# componentes1.net
KiCad netlist of a schematic drawn in EAGLE
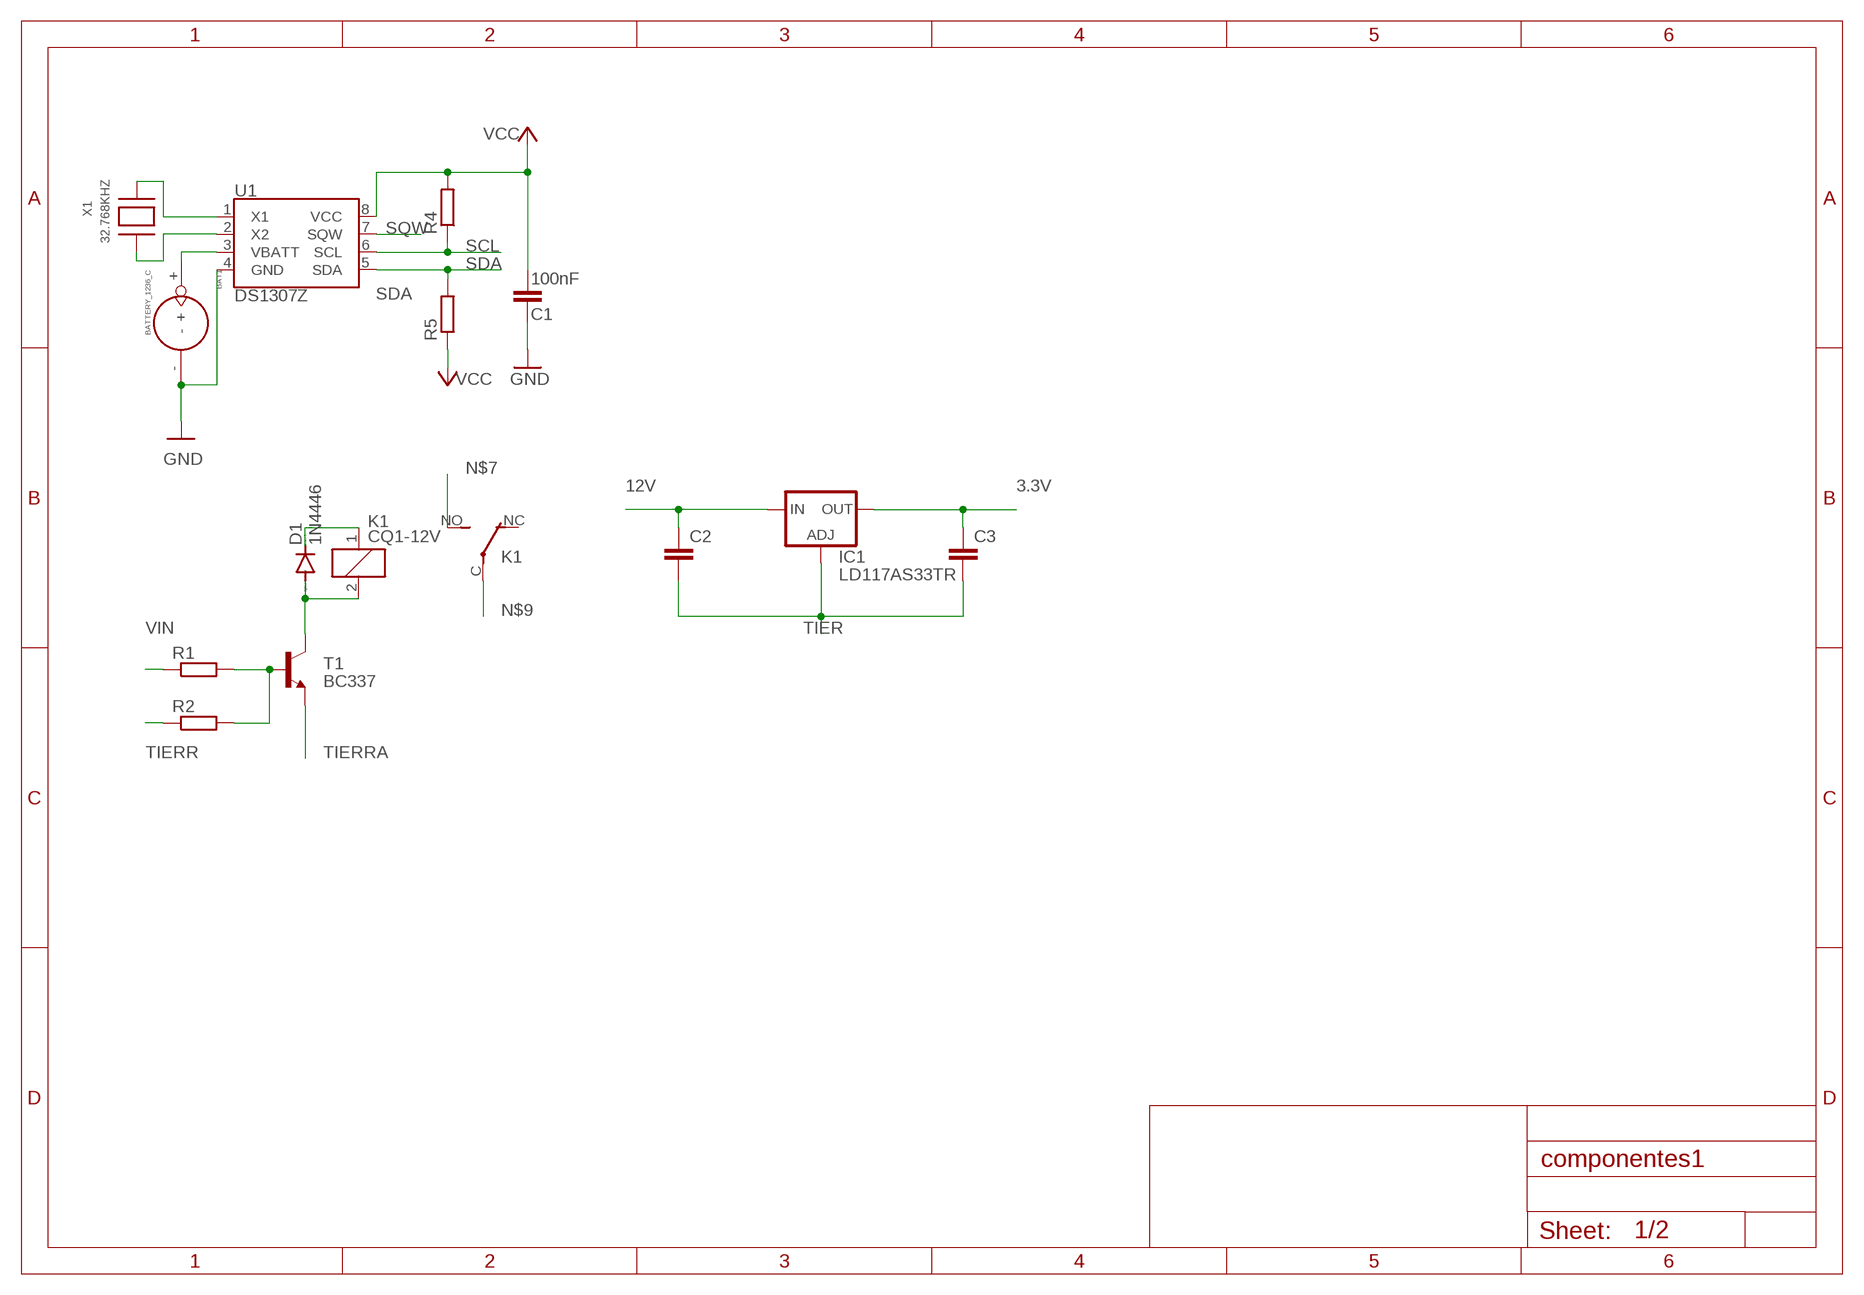
[diagram p0: schematic, sheet 1]
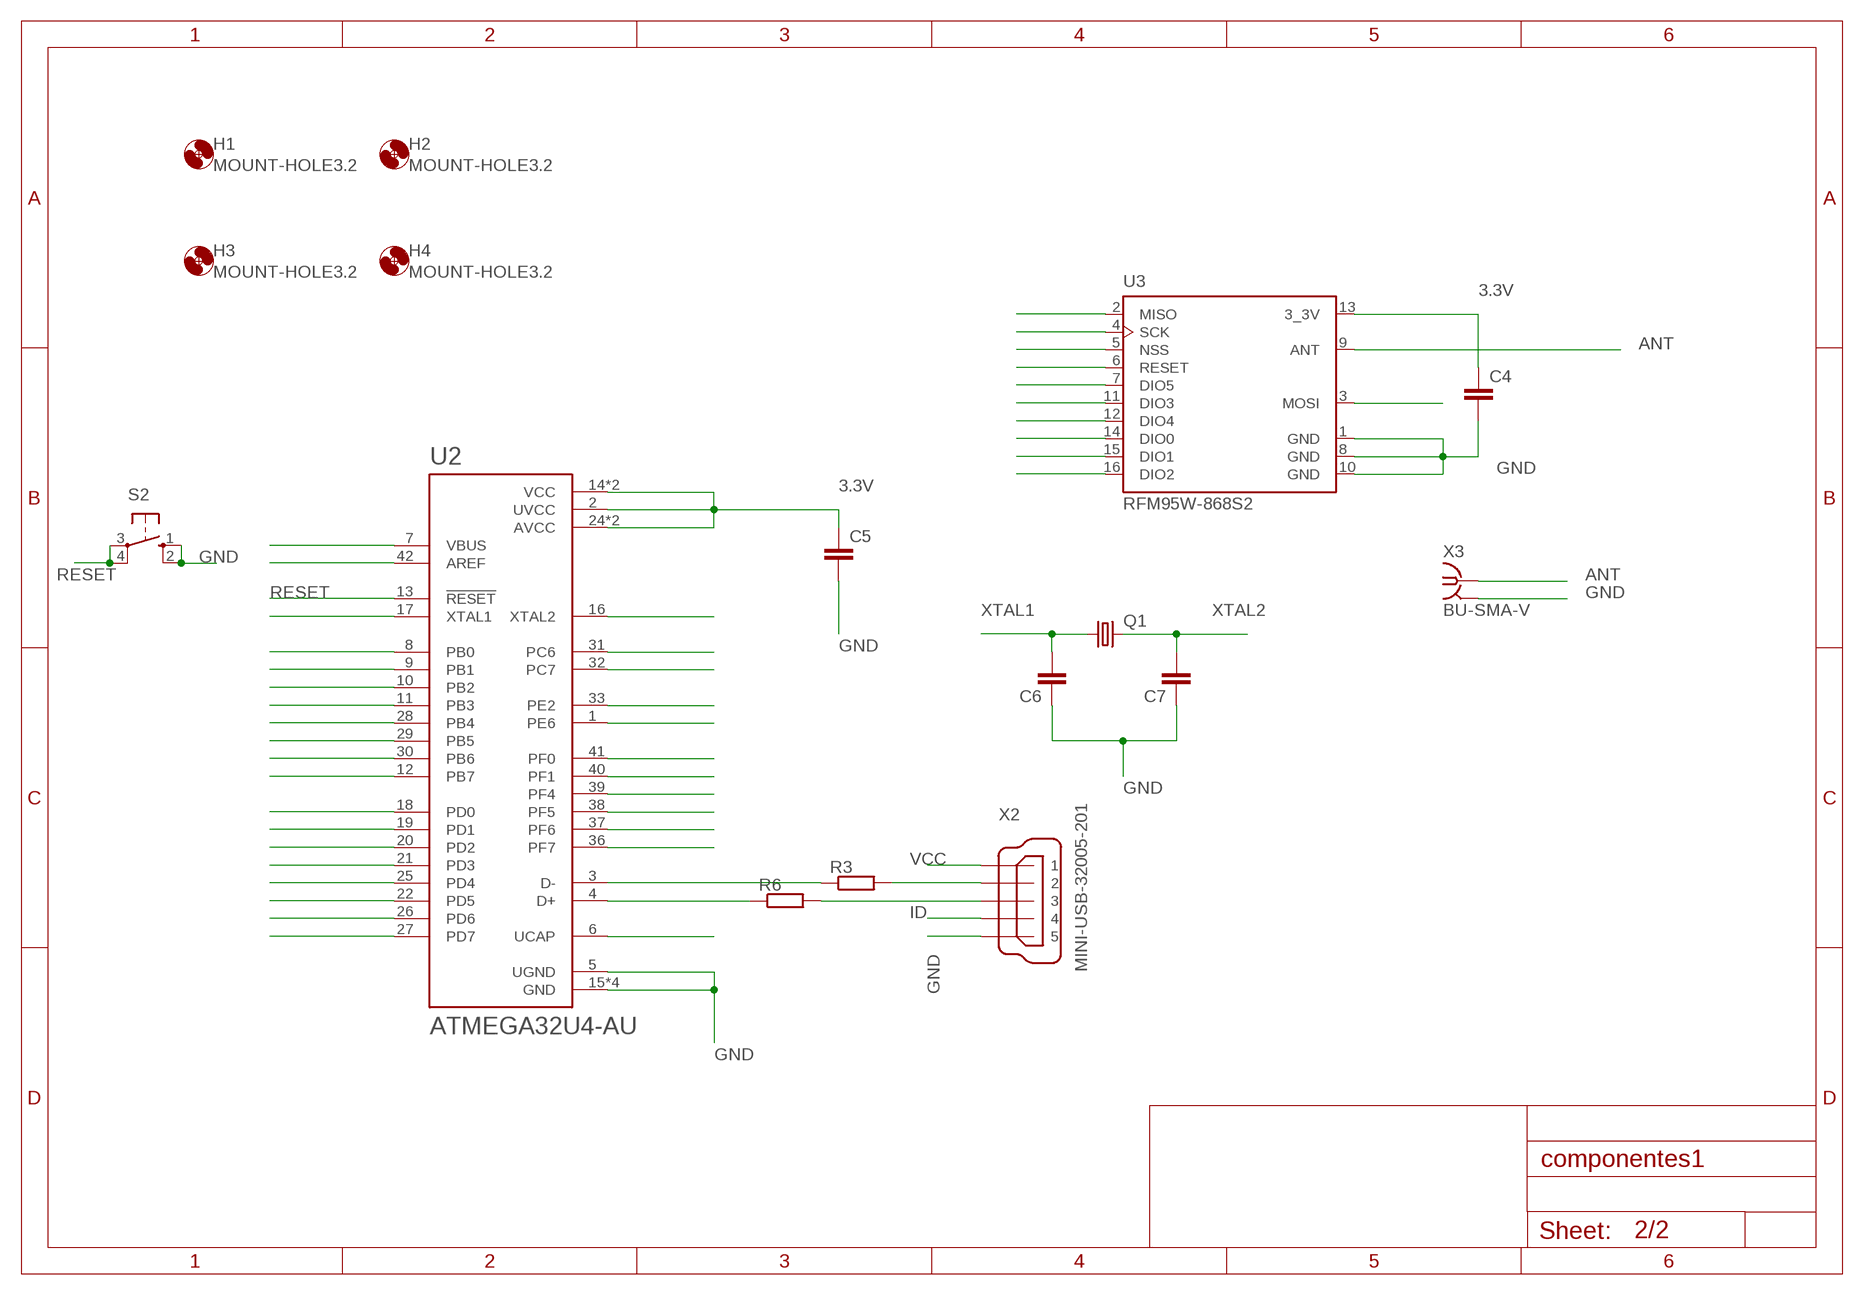
[diagram p1: schematic, sheet 2]

(export (version "E")
  (design (tool "Eeschema 10.0.6"))
  (components
    (comp (ref "BAT1")
      (value "BATTERY_1236_C")
      (footprint "eagle-import:BATTERY_1236_C")
      (libsource (lib "eagle-import") (part "BATTERY_1236_C"))
    )
    (comp (ref "C1")
      (value "100nF")
      (footprint "eagle-import:C0603")
      (libsource (lib "eagle-import") (part "C-EUC0603"))
    )
    (comp (ref "C2")
      (value "C-EU050-025X075")
      (footprint "eagle-import:C050-025X075")
      (libsource (lib "eagle-import") (part "rcl_334_C-EU050-025X075"))
    )
    (comp (ref "C3")
      (value "C-EU050-025X075")
      (footprint "eagle-import:C050-025X075")
      (libsource (lib "eagle-import") (part "rcl_334_C-EU050-025X075"))
    )
    (comp (ref "D1")
      (value "1N4446")
      (footprint "eagle-import:DO35-10")
      (libsource (lib "eagle-import") (part "1N4446"))
    )
    (comp (ref "IC1")
      (value "LD117AS33TR")
      (footprint "eagle-import:SOT223")
      (libsource (lib "eagle-import") (part "LD117A?S33TR"))
    )
    (comp (ref "K1")
      (value "CQ1-12V")
      (footprint "eagle-import:CQ1")
      (libsource (lib "eagle-import") (part "CQ1-12V"))
    )
    (comp (ref "R1")
      (value "R-EU_0207/10")
      (footprint "eagle-import:0207_10")
      (libsource (lib "eagle-import") (part "R-EU_0207/10"))
    )
    (comp (ref "R2")
      (value "R-EU_0207/10")
      (footprint "eagle-import:0207_10")
      (libsource (lib "eagle-import") (part "R-EU_0207/10"))
    )
    (comp (ref "R4")
      (value "R-EU_0207/10")
      (footprint "eagle-import:0207_10")
      (libsource (lib "eagle-import") (part "R-EU_0207/10"))
    )
    (comp (ref "R5")
      (value "R-EU_0207/10")
      (footprint "eagle-import:0207_10")
      (libsource (lib "eagle-import") (part "R-EU_0207/10"))
    )
    (comp (ref "T1")
      (value "BC337")
      (footprint "eagle-import:TO92")
      (libsource (lib "eagle-import") (part "BC337"))
    )
    (comp (ref "U1")
      (value "DS1307Z")
      (footprint "eagle-import:SO08-0.15")
      (libsource (lib "eagle-import") (part "DS1307Z"))
    )
    (comp (ref "X1")
      (value "32.768KHZ")
      (footprint "eagle-import:XTAL3215")
      (libsource (lib "eagle-import") (part "XTAL-3.2X1.5"))
    )
    (comp (ref "C4")
      (value "C-EU050-025X075")
      (footprint "eagle-import:C050-025X075")
      (libsource (lib "eagle-import") (part "rcl_334_C-EU050-025X075"))
    )
    (comp (ref "C5")
      (value "C-EU050-025X075")
      (footprint "eagle-import:C050-025X075")
      (libsource (lib "eagle-import") (part "rcl_334_C-EU050-025X075"))
    )
    (comp (ref "C6")
      (value "C-EU050-025X075")
      (footprint "eagle-import:C050-025X075")
      (libsource (lib "eagle-import") (part "rcl_334_C-EU050-025X075"))
    )
    (comp (ref "C7")
      (value "C-EU050-025X075")
      (footprint "eagle-import:C050-025X075")
      (libsource (lib "eagle-import") (part "rcl_334_C-EU050-025X075"))
    )
    (comp (ref "H1")
      (value "MOUNT-HOLE3.2")
      (footprint "eagle-import:3,2")
      (libsource (lib "eagle-import") (part "MOUNT-HOLE3.2"))
    )
    (comp (ref "H2")
      (value "MOUNT-HOLE3.2")
      (footprint "eagle-import:3,2")
      (libsource (lib "eagle-import") (part "MOUNT-HOLE3.2"))
    )
    (comp (ref "H3")
      (value "MOUNT-HOLE3.2")
      (footprint "eagle-import:3,2")
      (libsource (lib "eagle-import") (part "MOUNT-HOLE3.2"))
    )
    (comp (ref "H4")
      (value "MOUNT-HOLE3.2")
      (footprint "eagle-import:3,2")
      (libsource (lib "eagle-import") (part "MOUNT-HOLE3.2"))
    )
    (comp (ref "Q1")
      (value "CRYSTALHC49S")
      (footprint "eagle-import:HC49_S")
      (libsource (lib "eagle-import") (part "CRYSTALHC49S"))
    )
    (comp (ref "R3")
      (value "R-EU_0204/7")
      (footprint "eagle-import:0204_7")
      (libsource (lib "eagle-import") (part "R-EU_0204/7"))
    )
    (comp (ref "R6")
      (value "R-EU_0204/7")
      (footprint "eagle-import:0204_7")
      (libsource (lib "eagle-import") (part "R-EU_0204/7"))
    )
    (comp (ref "S2")
      (value "40-XX")
      (footprint "eagle-import:B3F-40XX")
      (fields (field (name "MF") "OMRON COMPONENTS USA") (field (name "MPN") "B3F-4000"))
      (libsource (lib "eagle-import") (part "40-XX"))
    )
    (comp (ref "U2")
      (value "ATMEGA32U4-AU")
      (footprint "eagle-import:QFP80P1200X1200X120-44N")
      (fields (field (name "MF") "Rochester Electronics, LLC"))
      (libsource (lib "eagle-import") (part "ATMEGA32U4-AU"))
    )
    (comp (ref "U3")
      (value "RFM95W-868S2")
      (footprint "eagle-import:XCVR_RFM95W-868S2")
      (fields (field (name "MF") "RF"))
      (libsource (lib "eagle-import") (part "RFM95W-868S2"))
    )
    (comp (ref "X2")
      (value "MINI-USB-32005-201")
      (footprint "eagle-import:32005-201")
      (libsource (lib "eagle-import") (part "MINI-USB-32005-201"))
    )
    (comp (ref "X3")
      (value "BU-SMA-V")
      (footprint "eagle-import:BU-SMA-V")
      (libsource (lib "eagle-import") (part "BU-SMA-V"))
    )
  )
  (nets
    (net (code "1") (name "3.3V") (class "Default")
      (node (ref "C3") (pin "1") (pinfunction "1_1") (pintype "passive"))
      (node (ref "C4") (pin "1") (pinfunction "1_1") (pintype "passive"))
      (node (ref "C5") (pin "1") (pinfunction "1_1") (pintype "passive"))
      (node (ref "IC1") (pin "4") (pinfunction "OUT_4") (pintype "passive"))
      (node (ref "U2") (pin "14") (pinfunction "VCC_14") (pintype "power_in"))
      (node (ref "U2") (pin "2") (pinfunction "UVCC_2") (pintype "power_in"))
      (node (ref "U2") (pin "24") (pinfunction "AVCC_24") (pintype "power_in"))
      (node (ref "U2") (pin "34") (pinfunction "VCC_34") (pintype "power_in"))
      (node (ref "U2") (pin "44") (pinfunction "AVCC_44") (pintype "power_in"))
      (node (ref "U3") (pin "13") (pinfunction "3_3V_13") (pintype "power_in"))
    )
    (net (code "2") (name "12V") (class "Default")
      (node (ref "C2") (pin "1") (pinfunction "1_1") (pintype "passive"))
      (node (ref "IC1") (pin "3") (pinfunction "IN_3") (pintype "input"))
    )
    (net (code "3") (name "ANT") (class "Default")
      (node (ref "U3") (pin "9") (pinfunction "ANT_9") (pintype "passive"))
      (node (ref "X3") (pin "1") (pinfunction "1_1") (pintype "passive"))
    )
    (net (code "4") (name "GND") (class "Default")
      (node (ref "BAT1") (pin "-") (pinfunction "-_-") (pintype "bidirectional"))
      (node (ref "C1") (pin "1") (pinfunction "1_1") (pintype "passive"))
      (node (ref "C4") (pin "2") (pinfunction "2_2") (pintype "passive"))
      (node (ref "C5") (pin "2") (pinfunction "2_2") (pintype "passive"))
      (node (ref "C6") (pin "1") (pinfunction "1_1") (pintype "passive"))
      (node (ref "C7") (pin "1") (pinfunction "1_1") (pintype "passive"))
      (node (ref "S2") (pin "1") (pinfunction "S_1") (pintype "passive"))
      (node (ref "S2") (pin "2") (pinfunction "S1_2") (pintype "passive"))
      (node (ref "U1") (pin "4") (pinfunction "GND_4") (pintype "bidirectional"))
      (node (ref "U2") (pin "15") (pinfunction "GND_15") (pintype "power_in"))
      (node (ref "U2") (pin "23") (pinfunction "GND_23") (pintype "power_in"))
      (node (ref "U2") (pin "35") (pinfunction "GND_35") (pintype "power_in"))
      (node (ref "U2") (pin "43") (pinfunction "GND_43") (pintype "power_in"))
      (node (ref "U2") (pin "5") (pinfunction "UGND_5") (pintype "power_in"))
      (node (ref "U3") (pin "1") (pinfunction "GND_1") (pintype "power_in"))
      (node (ref "U3") (pin "10") (pinfunction "GND_10") (pintype "power_in"))
      (node (ref "U3") (pin "8") (pinfunction "GND_8") (pintype "power_in"))
      (node (ref "X2") (pin "5") (pinfunction "5_5") (pintype "passive"))
      (node (ref "X3") (pin "2") (pinfunction "2_2") (pintype "passive"))
      (node (ref "X3") (pin "3") (pinfunction "2_3") (pintype "passive"))
      (node (ref "X3") (pin "4") (pinfunction "2_4") (pintype "passive"))
      (node (ref "X3") (pin "5") (pinfunction "2_5") (pintype "passive"))
    )
    (net (code "5") (name "ID") (class "Default")
      (node (ref "X2") (pin "4") (pinfunction "4_4") (pintype "passive"))
    )
    (net (code "6") (name "N$7") (class "Default")
      (node (ref "K1") (pin "NO") (pinfunction "S_NO") (pintype "passive"))
    )
    (net (code "7") (name "N$9") (class "Default")
      (node (ref "K1") (pin "C") (pinfunction "P_C") (pintype "passive"))
    )
    (net (code "8") (name "Net-(D1-PadC)") (class "Default")
      (node (ref "D1") (pin "C") (pinfunction "C_C") (pintype "passive"))
      (node (ref "K1") (pin "1") (pinfunction "1_1") (pintype "passive"))
    )
    (net (code "9") (name "Net-(R3-Pad2)") (class "Default")
      (node (ref "R3") (pin "2") (pinfunction "2_2") (pintype "passive"))
      (node (ref "X2") (pin "2") (pinfunction "2_2") (pintype "passive"))
    )
    (net (code "10") (name "Net-(R6-Pad2)") (class "Default")
      (node (ref "R6") (pin "2") (pinfunction "2_2") (pintype "passive"))
      (node (ref "X2") (pin "3") (pinfunction "3_3") (pintype "passive"))
    )
    (net (code "11") (name "Net-(T1-B)") (class "Default")
      (node (ref "R1") (pin "2") (pinfunction "2_2") (pintype "passive"))
      (node (ref "R2") (pin "2") (pinfunction "2_2") (pintype "passive"))
      (node (ref "T1") (pin "2") (pinfunction "B_2") (pintype "passive"))
    )
    (net (code "12") (name "Net-(T1-C)") (class "Default")
      (node (ref "D1") (pin "A") (pinfunction "A_A") (pintype "passive"))
      (node (ref "K1") (pin "2") (pinfunction "2_2") (pintype "passive"))
      (node (ref "T1") (pin "3") (pinfunction "C_3") (pintype "passive"))
    )
    (net (code "13") (name "Net-(U1-VBATT)") (class "Default")
      (node (ref "BAT1") (pin "+") (pinfunction "+_+") (pintype "bidirectional"))
      (node (ref "U1") (pin "3") (pinfunction "VBATT_3") (pintype "bidirectional"))
    )
    (net (code "14") (name "Net-(U1-X1)") (class "Default")
      (node (ref "U1") (pin "1") (pinfunction "X1_1") (pintype "bidirectional"))
      (node (ref "X1") (pin "P$2") (pinfunction "P$2_P$2") (pintype "bidirectional"))
    )
    (net (code "15") (name "Net-(U1-X2)") (class "Default")
      (node (ref "U1") (pin "2") (pinfunction "X2_2") (pintype "bidirectional"))
      (node (ref "X1") (pin "P$1") (pinfunction "P$1_P$1") (pintype "bidirectional"))
    )
    (net (code "16") (name "Net-(U2-D+)") (class "Default")
      (node (ref "R6") (pin "1") (pinfunction "1_1") (pintype "passive"))
      (node (ref "U2") (pin "4") (pinfunction "D+_4") (pintype "bidirectional"))
    )
    (net (code "17") (name "Net-(U2-D-)") (class "Default")
      (node (ref "R3") (pin "1") (pinfunction "1_1") (pintype "passive"))
      (node (ref "U2") (pin "3") (pinfunction "D-_3") (pintype "bidirectional"))
    )
    (net (code "18") (name "RESET") (class "Default")
      (node (ref "S2") (pin "3") (pinfunction "P_3") (pintype "passive"))
      (node (ref "S2") (pin "4") (pinfunction "P1_4") (pintype "passive"))
      (node (ref "U2") (pin "13") (pinfunction "~{RESET}_13") (pintype "input"))
    )
    (net (code "19") (name "SCL") (class "Default")
      (node (ref "R4") (pin "1") (pinfunction "1_1") (pintype "passive"))
      (node (ref "U1") (pin "6") (pinfunction "SCL_6") (pintype "bidirectional"))
    )
    (net (code "20") (name "SDA") (class "Default")
      (node (ref "R5") (pin "2") (pinfunction "2_2") (pintype "passive"))
      (node (ref "U1") (pin "5") (pinfunction "SDA_5") (pintype "bidirectional"))
    )
    (net (code "21") (name "SQW") (class "Default")
      (node (ref "U1") (pin "7") (pinfunction "SQW_7") (pintype "bidirectional"))
    )
    (net (code "22") (name "TIER") (class "Default")
      (node (ref "C2") (pin "2") (pinfunction "2_2") (pintype "passive"))
      (node (ref "C3") (pin "2") (pinfunction "2_2") (pintype "passive"))
      (node (ref "IC1") (pin "1") (pinfunction "ADJ_1") (pintype "input"))
    )
    (net (code "23") (name "TIERR") (class "Default")
      (node (ref "R2") (pin "1") (pinfunction "1_1") (pintype "passive"))
    )
    (net (code "24") (name "TIERRA") (class "Default")
      (node (ref "T1") (pin "1") (pinfunction "E_1") (pintype "passive"))
    )
    (net (code "25") (name "VCC") (class "Default")
      (node (ref "C1") (pin "2") (pinfunction "2_2") (pintype "passive"))
      (node (ref "R4") (pin "2") (pinfunction "2_2") (pintype "passive"))
      (node (ref "R5") (pin "1") (pinfunction "1_1") (pintype "passive"))
      (node (ref "U1") (pin "8") (pinfunction "VCC_8") (pintype "bidirectional"))
      (node (ref "X2") (pin "1") (pinfunction "1_1") (pintype "passive"))
    )
    (net (code "26") (name "VIN") (class "Default")
      (node (ref "R1") (pin "1") (pinfunction "1_1") (pintype "passive"))
    )
    (net (code "27") (name "XTAL1") (class "Default")
      (node (ref "C6") (pin "2") (pinfunction "2_2") (pintype "passive"))
      (node (ref "Q1") (pin "1") (pinfunction "1_1") (pintype "passive"))
    )
    (net (code "28") (name "XTAL2") (class "Default")
      (node (ref "C7") (pin "2") (pinfunction "2_2") (pintype "passive"))
      (node (ref "Q1") (pin "2") (pinfunction "2_2") (pintype "passive"))
    )
    (net (code "29") (name "unconnected-(K1B-O-PadNC)") (class "Default")
      (node (ref "K1") (pin "NC") (pinfunction "O_NC") (pintype "passive"))
    )
    (net (code "30") (name "unconnected-(U2-AREF-Pad42)") (class "Default")
      (node (ref "U2") (pin "42") (pinfunction "AREF_42") (pintype "input"))
    )
    (net (code "31") (name "unconnected-(U2-PB0-Pad8)") (class "Default")
      (node (ref "U2") (pin "8") (pinfunction "PB0_8") (pintype "bidirectional"))
    )
    (net (code "32") (name "unconnected-(U2-PB1-Pad9)") (class "Default")
      (node (ref "U2") (pin "9") (pinfunction "PB1_9") (pintype "bidirectional"))
    )
    (net (code "33") (name "unconnected-(U2-PB2-Pad10)") (class "Default")
      (node (ref "U2") (pin "10") (pinfunction "PB2_10") (pintype "bidirectional"))
    )
    (net (code "34") (name "unconnected-(U2-PB3-Pad11)") (class "Default")
      (node (ref "U2") (pin "11") (pinfunction "PB3_11") (pintype "bidirectional"))
    )
    (net (code "35") (name "unconnected-(U2-PB4-Pad28)") (class "Default")
      (node (ref "U2") (pin "28") (pinfunction "PB4_28") (pintype "bidirectional"))
    )
    (net (code "36") (name "unconnected-(U2-PB5-Pad29)") (class "Default")
      (node (ref "U2") (pin "29") (pinfunction "PB5_29") (pintype "bidirectional"))
    )
    (net (code "37") (name "unconnected-(U2-PB6-Pad30)") (class "Default")
      (node (ref "U2") (pin "30") (pinfunction "PB6_30") (pintype "bidirectional"))
    )
    (net (code "38") (name "unconnected-(U2-PB7-Pad12)") (class "Default")
      (node (ref "U2") (pin "12") (pinfunction "PB7_12") (pintype "bidirectional"))
    )
    (net (code "39") (name "unconnected-(U2-PC6-Pad31)") (class "Default")
      (node (ref "U2") (pin "31") (pinfunction "PC6_31") (pintype "bidirectional"))
    )
    (net (code "40") (name "unconnected-(U2-PC7-Pad32)") (class "Default")
      (node (ref "U2") (pin "32") (pinfunction "PC7_32") (pintype "bidirectional"))
    )
    (net (code "41") (name "unconnected-(U2-PD0-Pad18)") (class "Default")
      (node (ref "U2") (pin "18") (pinfunction "PD0_18") (pintype "bidirectional"))
    )
    (net (code "42") (name "unconnected-(U2-PD1-Pad19)") (class "Default")
      (node (ref "U2") (pin "19") (pinfunction "PD1_19") (pintype "bidirectional"))
    )
    (net (code "43") (name "unconnected-(U2-PD2-Pad20)") (class "Default")
      (node (ref "U2") (pin "20") (pinfunction "PD2_20") (pintype "bidirectional"))
    )
    (net (code "44") (name "unconnected-(U2-PD3-Pad21)") (class "Default")
      (node (ref "U2") (pin "21") (pinfunction "PD3_21") (pintype "bidirectional"))
    )
    (net (code "45") (name "unconnected-(U2-PD4-Pad25)") (class "Default")
      (node (ref "U2") (pin "25") (pinfunction "PD4_25") (pintype "bidirectional"))
    )
    (net (code "46") (name "unconnected-(U2-PD5-Pad22)") (class "Default")
      (node (ref "U2") (pin "22") (pinfunction "PD5_22") (pintype "bidirectional"))
    )
    (net (code "47") (name "unconnected-(U2-PD6-Pad26)") (class "Default")
      (node (ref "U2") (pin "26") (pinfunction "PD6_26") (pintype "bidirectional"))
    )
    (net (code "48") (name "unconnected-(U2-PD7-Pad27)") (class "Default")
      (node (ref "U2") (pin "27") (pinfunction "PD7_27") (pintype "bidirectional"))
    )
    (net (code "49") (name "unconnected-(U2-PE2-Pad33)") (class "Default")
      (node (ref "U2") (pin "33") (pinfunction "PE2_33") (pintype "bidirectional"))
    )
    (net (code "50") (name "unconnected-(U2-PE6-Pad1)") (class "Default")
      (node (ref "U2") (pin "1") (pinfunction "PE6_1") (pintype "bidirectional"))
    )
    (net (code "51") (name "unconnected-(U2-PF0-Pad41)") (class "Default")
      (node (ref "U2") (pin "41") (pinfunction "PF0_41") (pintype "bidirectional"))
    )
    (net (code "52") (name "unconnected-(U2-PF1-Pad40)") (class "Default")
      (node (ref "U2") (pin "40") (pinfunction "PF1_40") (pintype "bidirectional"))
    )
    (net (code "53") (name "unconnected-(U2-PF4-Pad39)") (class "Default")
      (node (ref "U2") (pin "39") (pinfunction "PF4_39") (pintype "bidirectional"))
    )
    (net (code "54") (name "unconnected-(U2-PF5-Pad38)") (class "Default")
      (node (ref "U2") (pin "38") (pinfunction "PF5_38") (pintype "bidirectional"))
    )
    (net (code "55") (name "unconnected-(U2-PF6-Pad37)") (class "Default")
      (node (ref "U2") (pin "37") (pinfunction "PF6_37") (pintype "bidirectional"))
    )
    (net (code "56") (name "unconnected-(U2-PF7-Pad36)") (class "Default")
      (node (ref "U2") (pin "36") (pinfunction "PF7_36") (pintype "bidirectional"))
    )
    (net (code "57") (name "unconnected-(U2-UCAP-Pad6)") (class "Default")
      (node (ref "U2") (pin "6") (pinfunction "UCAP_6") (pintype "passive"))
    )
    (net (code "58") (name "unconnected-(U2-VBUS-Pad7)") (class "Default")
      (node (ref "U2") (pin "7") (pinfunction "VBUS_7") (pintype "input"))
    )
    (net (code "59") (name "unconnected-(U2-XTAL1-Pad17)") (class "Default")
      (node (ref "U2") (pin "17") (pinfunction "XTAL1_17") (pintype "input"))
    )
    (net (code "60") (name "unconnected-(U2-XTAL2-Pad16)") (class "Default")
      (node (ref "U2") (pin "16") (pinfunction "XTAL2_16") (pintype "output"))
    )
    (net (code "61") (name "unconnected-(U3-DIO0-Pad14)") (class "Default")
      (node (ref "U3") (pin "14") (pinfunction "DIO0_14") (pintype "bidirectional"))
    )
    (net (code "62") (name "unconnected-(U3-DIO1-Pad15)") (class "Default")
      (node (ref "U3") (pin "15") (pinfunction "DIO1_15") (pintype "bidirectional"))
    )
    (net (code "63") (name "unconnected-(U3-DIO2-Pad16)") (class "Default")
      (node (ref "U3") (pin "16") (pinfunction "DIO2_16") (pintype "bidirectional"))
    )
    (net (code "64") (name "unconnected-(U3-DIO3-Pad11)") (class "Default")
      (node (ref "U3") (pin "11") (pinfunction "DIO3_11") (pintype "bidirectional"))
    )
    (net (code "65") (name "unconnected-(U3-DIO4-Pad12)") (class "Default")
      (node (ref "U3") (pin "12") (pinfunction "DIO4_12") (pintype "bidirectional"))
    )
    (net (code "66") (name "unconnected-(U3-DIO5-Pad7)") (class "Default")
      (node (ref "U3") (pin "7") (pinfunction "DIO5_7") (pintype "bidirectional"))
    )
    (net (code "67") (name "unconnected-(U3-MISO-Pad2)") (class "Default")
      (node (ref "U3") (pin "2") (pinfunction "MISO_2") (pintype "input"))
    )
    (net (code "68") (name "unconnected-(U3-MOSI-Pad3)") (class "Default")
      (node (ref "U3") (pin "3") (pinfunction "MOSI_3") (pintype "output"))
    )
    (net (code "69") (name "unconnected-(U3-NSS-Pad5)") (class "Default")
      (node (ref "U3") (pin "5") (pinfunction "NSS_5") (pintype "input"))
    )
    (net (code "70") (name "unconnected-(U3-RESET-Pad6)") (class "Default")
      (node (ref "U3") (pin "6") (pinfunction "RESET_6") (pintype "bidirectional"))
    )
    (net (code "71") (name "unconnected-(U3-SCK-Pad4)") (class "Default")
      (node (ref "U3") (pin "4") (pinfunction "SCK_4") (pintype "input"))
    )
  )
)
